# Planta_1_inestable.net
KiCad netlist of a schematic drawn in EAGLE
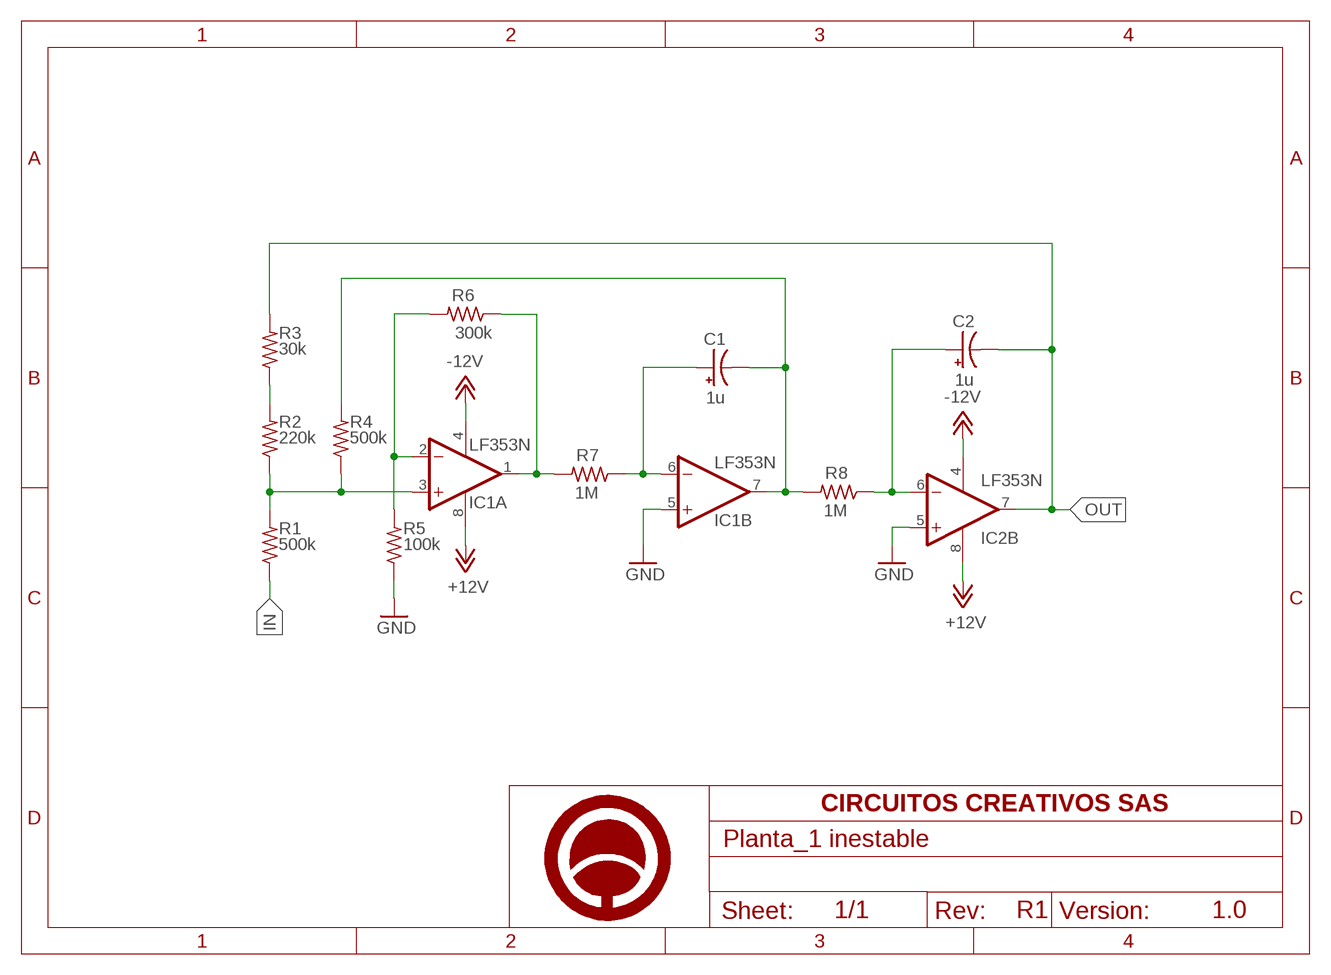
[diagram p0: schematic, sheet 1]

(export (version "E")
  (design (tool "Eeschema 10.0.6"))
  (components
    (comp (ref "C1")
      (value "1u")
      (footprint "eagle-import:E2-5")
      (libsource (lib "eagle-import") (part "CPOL-USE2-5"))
    )
    (comp (ref "C2")
      (value "1u")
      (footprint "eagle-import:E2-5")
      (libsource (lib "eagle-import") (part "CPOL-USE2-5"))
    )
    (comp (ref "IC1")
      (value "LF353N")
      (footprint "eagle-import:DIL08")
      (libsource (lib "eagle-import") (part "LF353N"))
    )
    (comp (ref "IC2")
      (value "LF353N")
      (footprint "eagle-import:DIL08")
      (libsource (lib "eagle-import") (part "LF353N"))
    )
    (comp (ref "R1")
      (value "500k")
      (footprint "eagle-import:0204_7")
      (libsource (lib "eagle-import") (part "R-US_0204/7"))
    )
    (comp (ref "R2")
      (value "220k")
      (footprint "eagle-import:0204_7")
      (libsource (lib "eagle-import") (part "R-US_0204/7"))
    )
    (comp (ref "R3")
      (value "30k")
      (footprint "eagle-import:0204_7")
      (libsource (lib "eagle-import") (part "R-US_0204/7"))
    )
    (comp (ref "R4")
      (value "500k")
      (footprint "eagle-import:0204_7")
      (libsource (lib "eagle-import") (part "R-US_0204/7"))
    )
    (comp (ref "R5")
      (value "100k")
      (footprint "eagle-import:0204_7")
      (libsource (lib "eagle-import") (part "R-US_0204/7"))
    )
    (comp (ref "R6")
      (value "300k")
      (footprint "eagle-import:0204_7")
      (libsource (lib "eagle-import") (part "R-US_0204/7"))
    )
    (comp (ref "R7")
      (value "1M")
      (footprint "eagle-import:0204_7")
      (libsource (lib "eagle-import") (part "R-US_0204/7"))
    )
    (comp (ref "R8")
      (value "1M")
      (footprint "eagle-import:0204_7")
      (libsource (lib "eagle-import") (part "R-US_0204/7"))
    )
    (comp (ref "U$1")
      (value "LOGO")
      (footprint "eagle-import:LOGO")
      (libsource (lib "eagle-import") (part "LOGO"))
    )
  )
  (nets
    (net (code "1") (name "+12V") (class "Default")
      (node (ref "IC1") (pin "8") (pinfunction "V+_8") (pintype "power_in"))
      (node (ref "IC2") (pin "8") (pinfunction "V+_8") (pintype "power_in"))
    )
    (net (code "2") (name "-12V") (class "Default")
      (node (ref "IC1") (pin "4") (pinfunction "V-_4") (pintype "power_in"))
      (node (ref "IC2") (pin "4") (pinfunction "V-_4") (pintype "power_in"))
    )
    (net (code "3") (name "GND") (class "Default")
      (node (ref "IC1") (pin "5") (pinfunction "+IN_5") (pintype "input"))
      (node (ref "IC2") (pin "5") (pinfunction "+IN_5") (pintype "input"))
      (node (ref "R5") (pin "1") (pinfunction "1_1") (pintype "passive"))
    )
    (net (code "4") (name "IN") (class "Default")
      (node (ref "R1") (pin "1") (pinfunction "1_1") (pintype "passive"))
    )
    (net (code "5") (name "Net-(IC1A-+IN)") (class "Default")
      (node (ref "IC1") (pin "3") (pinfunction "+IN_3") (pintype "input"))
      (node (ref "R1") (pin "2") (pinfunction "2_2") (pintype "passive"))
      (node (ref "R2") (pin "1") (pinfunction "1_1") (pintype "passive"))
      (node (ref "R4") (pin "1") (pinfunction "1_1") (pintype "passive"))
    )
    (net (code "6") (name "Net-(IC1A--IN)") (class "Default")
      (node (ref "IC1") (pin "2") (pinfunction "-IN_2") (pintype "input"))
      (node (ref "R5") (pin "2") (pinfunction "2_2") (pintype "passive"))
      (node (ref "R6") (pin "2") (pinfunction "2_2") (pintype "passive"))
    )
    (net (code "7") (name "Net-(IC1A-OUT)") (class "Default")
      (node (ref "IC1") (pin "1") (pinfunction "OUT_1") (pintype "output"))
      (node (ref "R6") (pin "1") (pinfunction "1_1") (pintype "passive"))
      (node (ref "R7") (pin "2") (pinfunction "2_2") (pintype "passive"))
    )
    (net (code "8") (name "Net-(IC1B--IN)") (class "Default")
      (node (ref "C1") (pin "+") (pinfunction "+_+") (pintype "passive"))
      (node (ref "IC1") (pin "6") (pinfunction "-IN_6") (pintype "input"))
      (node (ref "R7") (pin "1") (pinfunction "1_1") (pintype "passive"))
    )
    (net (code "9") (name "Net-(IC1B-OUT)") (class "Default")
      (node (ref "C1") (pin "-") (pinfunction "-_-") (pintype "passive"))
      (node (ref "IC1") (pin "7") (pinfunction "OUT_7") (pintype "output"))
      (node (ref "R4") (pin "2") (pinfunction "2_2") (pintype "passive"))
      (node (ref "R8") (pin "2") (pinfunction "2_2") (pintype "passive"))
    )
    (net (code "10") (name "Net-(IC2B--IN)") (class "Default")
      (node (ref "C2") (pin "+") (pinfunction "+_+") (pintype "passive"))
      (node (ref "IC2") (pin "6") (pinfunction "-IN_6") (pintype "input"))
      (node (ref "R8") (pin "1") (pinfunction "1_1") (pintype "passive"))
    )
    (net (code "11") (name "Net-(R2-Pad2)") (class "Default")
      (node (ref "R2") (pin "2") (pinfunction "2_2") (pintype "passive"))
      (node (ref "R3") (pin "1") (pinfunction "1_1") (pintype "passive"))
    )
    (net (code "12") (name "OUT") (class "Default")
      (node (ref "C2") (pin "-") (pinfunction "-_-") (pintype "passive"))
      (node (ref "IC2") (pin "7") (pinfunction "OUT_7") (pintype "output"))
      (node (ref "R3") (pin "2") (pinfunction "2_2") (pintype "passive"))
    )
  )
)
